# MCU.net
KiCad netlist of a schematic drawn in Altium Designer
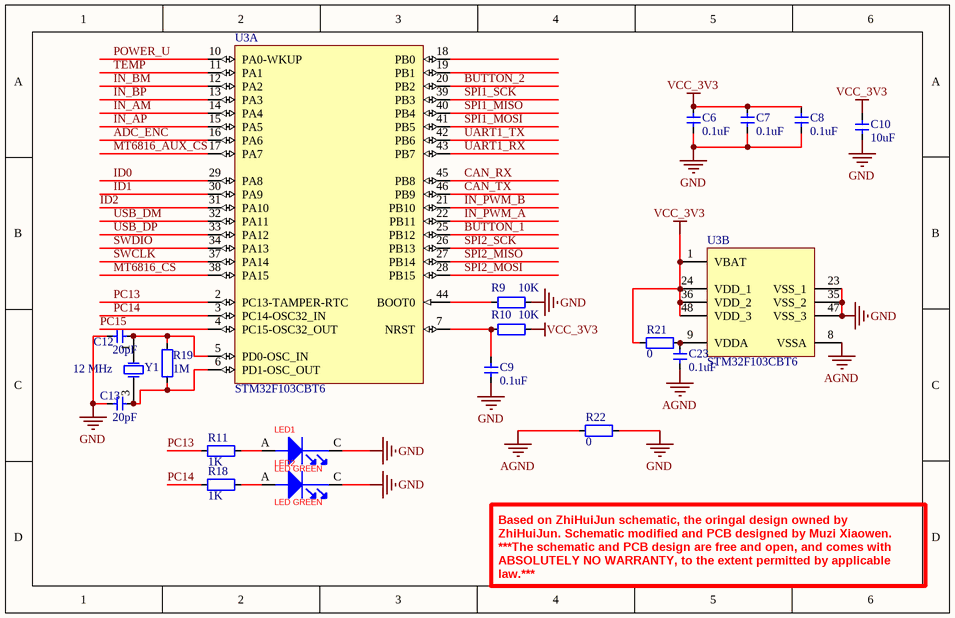
[diagram p0: MCU.SchDoc]

(export (version "E")
  (design (tool "Eeschema 10.0.6"))
  (components
    (comp (ref "C6")
      (value "0.1uF")
      (footprint "motor42-lib:CAP_0402")
      (description "Capacitor")
      (libsource (lib "MyPcbLib") (part "电容-0402"))
    )
    (comp (ref "C7")
      (value "0.1uF")
      (footprint "motor42-lib:CAP_0402")
      (description "Capacitor")
      (libsource (lib "MyPcbLib") (part "电容-0402"))
    )
    (comp (ref "C8")
      (value "0.1uF")
      (footprint "motor42-lib:CAP_0402")
      (description "Capacitor")
      (libsource (lib "MyPcbLib") (part "电容-0402"))
    )
    (comp (ref "C9")
      (value "0.1uF")
      (footprint "motor42-lib:CAP_0402")
      (description "Capacitor")
      (libsource (lib "MyPcbLib") (part "电容-0402"))
    )
    (comp (ref "C10")
      (value "10uF")
      (footprint "CAP_0402")
      (description "Capacitor")
      (libsource (lib "MyPcbLib") (part "电容-0402"))
    )
    (comp (ref "C12")
      (value "20pF")
      (footprint "motor42-lib:CAP_0402")
      (description "Capacitor")
      (libsource (lib "MyPcbLib") (part "电容-0402"))
    )
    (comp (ref "C13")
      (value "20pF")
      (footprint "motor42-lib:CAP_0402")
      (description "Capacitor")
      (libsource (lib "MyPcbLib") (part "电容-0402"))
    )
    (comp (ref "C23")
      (value "0.1uF")
      (footprint "motor42-lib:CAP_0402")
      (description "Capacitor")
      (libsource (lib "MyPcbLib") (part "电容-0402"))
    )
    (comp (ref "LED1")
      (value "LED GREEN")
      (footprint "LED-0603")
      (description "LED GRN SGL RA 25mA 4.1V SMD")
      (libsource (lib "*") (part "LED"))
    )
    (comp (ref "LED2")
      (value "LED GREEN")
      (footprint "LED-0603")
      (description "LED GRN SGL RA 25mA 4.1V SMD")
      (libsource (lib "*") (part "LED"))
    )
    (comp (ref "R9")
      (value "10K")
      (footprint "RES_0402")
      (description "Resistor")
      (libsource (lib "") (part "电阻-0402_1"))
    )
    (comp (ref "R10")
      (value "10K")
      (footprint "RES_0402")
      (description "Resistor")
      (libsource (lib "") (part "电阻-0402_1"))
    )
    (comp (ref "R11")
      (value "1K")
      (footprint "RES_0402")
      (description "Resistor")
      (libsource (lib "") (part "电阻-0402_1"))
    )
    (comp (ref "R18")
      (value "1K")
      (footprint "RES_0402")
      (description "Resistor")
      (libsource (lib "") (part "电阻-0402_1"))
    )
    (comp (ref "R19")
      (value "1M")
      (footprint "RES_0402")
      (description "Resistor")
      (libsource (lib "") (part "电阻-0402_2"))
    )
    (comp (ref "R21")
      (value "0")
      (footprint "RES_0402")
      (description "Resistor")
      (libsource (lib "MyPcbLib") (part "电阻-0402"))
    )
    (comp (ref "R22")
      (value "0")
      (footprint "RES_0402")
      (description "Resistor")
      (libsource (lib "MyPcbLib") (part "电阻-0402"))
    )
    (comp (ref "U3")
      (value "STM32F103CBT6")
      (footprint "LQFP-48")
      (libsource (lib "STMicroelectronics STM32 F1") (part "STM32F103CBT6"))
    )
    (comp (ref "Y1")
      (value "12 MHz")
      (footprint "LC-SMD-3225_4P")
      (description "Crystal")
      (fields (field (name "Comment") "XTAL-4"))
      (libsource (lib "rpi") (part "XTAL-4"))
    )
  )
  (nets
    (net (code "1") (name "/ADC_ENC") (class "Default")
      (node (ref "U3") (pin "16") (pinfunction "PA6_16") (pintype "bidirectional"))
    )
    (net (code "2") (name "/BUTTON_1") (class "Default")
      (node (ref "U3") (pin "25") (pinfunction "PB12_25") (pintype "bidirectional"))
    )
    (net (code "3") (name "/BUTTON_2") (class "Default")
      (node (ref "U3") (pin "20") (pinfunction "PB2_20") (pintype "bidirectional"))
    )
    (net (code "4") (name "/CAN_RX") (class "Default")
      (node (ref "U3") (pin "45") (pinfunction "PB8_45") (pintype "bidirectional"))
    )
    (net (code "5") (name "/CAN_TX") (class "Default")
      (node (ref "U3") (pin "46") (pinfunction "PB9_46") (pintype "bidirectional"))
    )
    (net (code "6") (name "/ID0") (class "Default")
      (node (ref "U3") (pin "29") (pinfunction "PA8_29") (pintype "bidirectional"))
    )
    (net (code "7") (name "/ID1") (class "Default")
      (node (ref "U3") (pin "30") (pinfunction "PA9_30") (pintype "bidirectional"))
    )
    (net (code "8") (name "/ID2") (class "Default")
      (node (ref "U3") (pin "31") (pinfunction "PA10_31") (pintype "bidirectional"))
    )
    (net (code "9") (name "/IN_AM") (class "Default")
      (node (ref "U3") (pin "14") (pinfunction "PA4_14") (pintype "bidirectional"))
    )
    (net (code "10") (name "/IN_AP") (class "Default")
      (node (ref "U3") (pin "15") (pinfunction "PA5_15") (pintype "bidirectional"))
    )
    (net (code "11") (name "/IN_BM") (class "Default")
      (node (ref "U3") (pin "12") (pinfunction "PA2_12") (pintype "bidirectional"))
    )
    (net (code "12") (name "/IN_BP") (class "Default")
      (node (ref "U3") (pin "13") (pinfunction "PA3_13") (pintype "bidirectional"))
    )
    (net (code "13") (name "/IN_PWM_A") (class "Default")
      (node (ref "U3") (pin "22") (pinfunction "PB11_22") (pintype "bidirectional"))
    )
    (net (code "14") (name "/IN_PWM_B") (class "Default")
      (node (ref "U3") (pin "21") (pinfunction "PB10_21") (pintype "bidirectional"))
    )
    (net (code "15") (name "/MT6816_AUX_CS") (class "Default")
      (node (ref "U3") (pin "17") (pinfunction "PA7_17") (pintype "bidirectional"))
    )
    (net (code "16") (name "/MT6816_CS") (class "Default")
      (node (ref "U3") (pin "38") (pinfunction "PA15_38") (pintype "bidirectional"))
    )
    (net (code "17") (name "/PC13") (class "Default")
      (node (ref "R11") (pin "1") (pinfunction "1_1") (pintype "passive"))
      (node (ref "U3") (pin "2") (pinfunction "PC13-TAMPER-RTC_2") (pintype "bidirectional"))
    )
    (net (code "18") (name "/PC14") (class "Default")
      (node (ref "R18") (pin "1") (pinfunction "1_1") (pintype "passive"))
      (node (ref "U3") (pin "3") (pinfunction "PC14-OSC32_IN_3") (pintype "bidirectional"))
    )
    (net (code "19") (name "/PC15") (class "Default")
      (node (ref "U3") (pin "4") (pinfunction "PC15-OSC32_OUT_4") (pintype "bidirectional"))
    )
    (net (code "20") (name "/POWER_U") (class "Default")
      (node (ref "U3") (pin "10") (pinfunction "PA0-WKUP_10") (pintype "bidirectional"))
    )
    (net (code "21") (name "/SPI1_MISO") (class "Default")
      (node (ref "U3") (pin "40") (pinfunction "PB4_40") (pintype "bidirectional"))
    )
    (net (code "22") (name "/SPI1_MOSI") (class "Default")
      (node (ref "U3") (pin "41") (pinfunction "PB5_41") (pintype "bidirectional"))
    )
    (net (code "23") (name "/SPI1_SCK") (class "Default")
      (node (ref "U3") (pin "39") (pinfunction "PB3_39") (pintype "bidirectional"))
    )
    (net (code "24") (name "/SPI2_MISO") (class "Default")
      (node (ref "U3") (pin "27") (pinfunction "PB14_27") (pintype "bidirectional"))
    )
    (net (code "25") (name "/SPI2_MOSI") (class "Default")
      (node (ref "U3") (pin "28") (pinfunction "PB15_28") (pintype "bidirectional"))
    )
    (net (code "26") (name "/SPI2_SCK") (class "Default")
      (node (ref "U3") (pin "26") (pinfunction "PB13_26") (pintype "bidirectional"))
    )
    (net (code "27") (name "/SWCLK") (class "Default")
      (node (ref "U3") (pin "37") (pinfunction "PA14_37") (pintype "bidirectional"))
    )
    (net (code "28") (name "/SWDIO") (class "Default")
      (node (ref "U3") (pin "34") (pinfunction "PA13_34") (pintype "bidirectional"))
    )
    (net (code "29") (name "/TEMP") (class "Default")
      (node (ref "U3") (pin "11") (pinfunction "PA1_11") (pintype "bidirectional"))
    )
    (net (code "30") (name "/UART1_RX") (class "Default")
      (node (ref "U3") (pin "43") (pinfunction "PB7_43") (pintype "bidirectional"))
    )
    (net (code "31") (name "/UART1_TX") (class "Default")
      (node (ref "U3") (pin "42") (pinfunction "PB6_42") (pintype "bidirectional"))
    )
    (net (code "32") (name "/USB_DM") (class "Default")
      (node (ref "U3") (pin "32") (pinfunction "PA11_32") (pintype "bidirectional"))
    )
    (net (code "33") (name "/USB_DP") (class "Default")
      (node (ref "U3") (pin "33") (pinfunction "PA12_33") (pintype "bidirectional"))
    )
    (net (code "34") (name "AGND") (class "Default")
      (node (ref "C23") (pin "1") (pinfunction "1_1") (pintype "passive"))
      (node (ref "R22") (pin "2") (pinfunction "2_2") (pintype "passive"))
      (node (ref "U3") (pin "8") (pinfunction "VSSA_8") (pintype "power_in"))
    )
    (net (code "35") (name "GND") (class "Default")
      (node (ref "C10") (pin "1") (pinfunction "1_1") (pintype "passive"))
      (node (ref "C12") (pin "2") (pinfunction "2_2") (pintype "passive"))
      (node (ref "C13") (pin "2") (pinfunction "2_2") (pintype "passive"))
      (node (ref "C6") (pin "1") (pinfunction "1_1") (pintype "passive"))
      (node (ref "C7") (pin "1") (pinfunction "1_1") (pintype "passive"))
      (node (ref "C8") (pin "1") (pinfunction "1_1") (pintype "passive"))
      (node (ref "C9") (pin "1") (pinfunction "1_1") (pintype "passive"))
      (node (ref "LED1") (pin "C") (pinfunction "CATHODE_C") (pintype "passive"))
      (node (ref "LED2") (pin "C") (pinfunction "CATHODE_C") (pintype "passive"))
      (node (ref "R22") (pin "1") (pinfunction "1_1") (pintype "passive"))
      (node (ref "R9") (pin "2") (pinfunction "2_2") (pintype "passive"))
      (node (ref "U3") (pin "23") (pinfunction "VSS_1_23") (pintype "power_in"))
      (node (ref "U3") (pin "35") (pinfunction "VSS_2_35") (pintype "power_in"))
      (node (ref "U3") (pin "47") (pinfunction "VSS_3_47") (pintype "power_in"))
    )
    (net (code "36") (name "Net-(LED1-ANODE)") (class "Default")
      (node (ref "LED1") (pin "A") (pinfunction "ANODE_A") (pintype "passive"))
      (node (ref "R11") (pin "2") (pinfunction "2_2") (pintype "passive"))
    )
    (net (code "37") (name "Net-(LED2-ANODE)") (class "Default")
      (node (ref "LED2") (pin "A") (pinfunction "ANODE_A") (pintype "passive"))
      (node (ref "R18") (pin "2") (pinfunction "2_2") (pintype "passive"))
    )
    (net (code "38") (name "Net-(U3A-BOOT0)") (class "Default")
      (node (ref "R9") (pin "1") (pinfunction "1_1") (pintype "passive"))
      (node (ref "U3") (pin "44") (pinfunction "BOOT0_44") (pintype "input"))
    )
    (net (code "39") (name "Net-(U3A-NRST)") (class "Default")
      (node (ref "C9") (pin "2") (pinfunction "2_2") (pintype "passive"))
      (node (ref "R10") (pin "1") (pinfunction "1_1") (pintype "passive"))
      (node (ref "U3") (pin "7") (pinfunction "NRST_7") (pintype "bidirectional"))
    )
    (net (code "40") (name "Net-(U3A-PD0-OSC_IN)") (class "Default")
      (node (ref "C12") (pin "1") (pinfunction "1_1") (pintype "passive"))
      (node (ref "R19") (pin "2") (pinfunction "2_2") (pintype "passive"))
      (node (ref "U3") (pin "5") (pinfunction "PD0-OSC_IN_5") (pintype "bidirectional"))
      (node (ref "Y1") (pin "1") (pinfunction "OSC1_1") (pintype "passive"))
    )
    (net (code "41") (name "Net-(U3A-PD1-OSC_OUT)") (class "Default")
      (node (ref "C13") (pin "1") (pinfunction "1_1") (pintype "passive"))
      (node (ref "R19") (pin "1") (pinfunction "1_1") (pintype "passive"))
      (node (ref "U3") (pin "6") (pinfunction "PD1-OSC_OUT_6") (pintype "bidirectional"))
      (node (ref "Y1") (pin "3") (pinfunction "OSC2_3") (pintype "passive"))
    )
    (net (code "42") (name "Net-(U3B-VDDA)") (class "Default")
      (node (ref "C23") (pin "2") (pinfunction "2_2") (pintype "passive"))
      (node (ref "R21") (pin "1") (pinfunction "1_1") (pintype "passive"))
      (node (ref "U3") (pin "9") (pinfunction "VDDA_9") (pintype "power_in"))
    )
    (net (code "43") (name "VCC_3V3") (class "Default")
      (node (ref "C10") (pin "2") (pinfunction "2_2") (pintype "passive"))
      (node (ref "C6") (pin "2") (pinfunction "2_2") (pintype "passive"))
      (node (ref "C7") (pin "2") (pinfunction "2_2") (pintype "passive"))
      (node (ref "C8") (pin "2") (pinfunction "2_2") (pintype "passive"))
      (node (ref "R10") (pin "2") (pinfunction "2_2") (pintype "passive"))
      (node (ref "R21") (pin "2") (pinfunction "2_2") (pintype "passive"))
      (node (ref "U3") (pin "1") (pinfunction "VBAT_1") (pintype "power_in"))
      (node (ref "U3") (pin "24") (pinfunction "VDD_1_24") (pintype "power_in"))
      (node (ref "U3") (pin "36") (pinfunction "VDD_2_36") (pintype "power_in"))
      (node (ref "U3") (pin "48") (pinfunction "VDD_3_48") (pintype "power_in"))
    )
    (net (code "44") (name "unconnected-(U3A-PB0-Pad18)") (class "Default")
      (node (ref "U3") (pin "18") (pinfunction "PB0_18") (pintype "bidirectional"))
    )
    (net (code "45") (name "unconnected-(U3A-PB1-Pad19)") (class "Default")
      (node (ref "U3") (pin "19") (pinfunction "PB1_19") (pintype "bidirectional"))
    )
  )
)
